# BaseModuleTop.net
KiCad netlist of a schematic drawn in Altium Designer
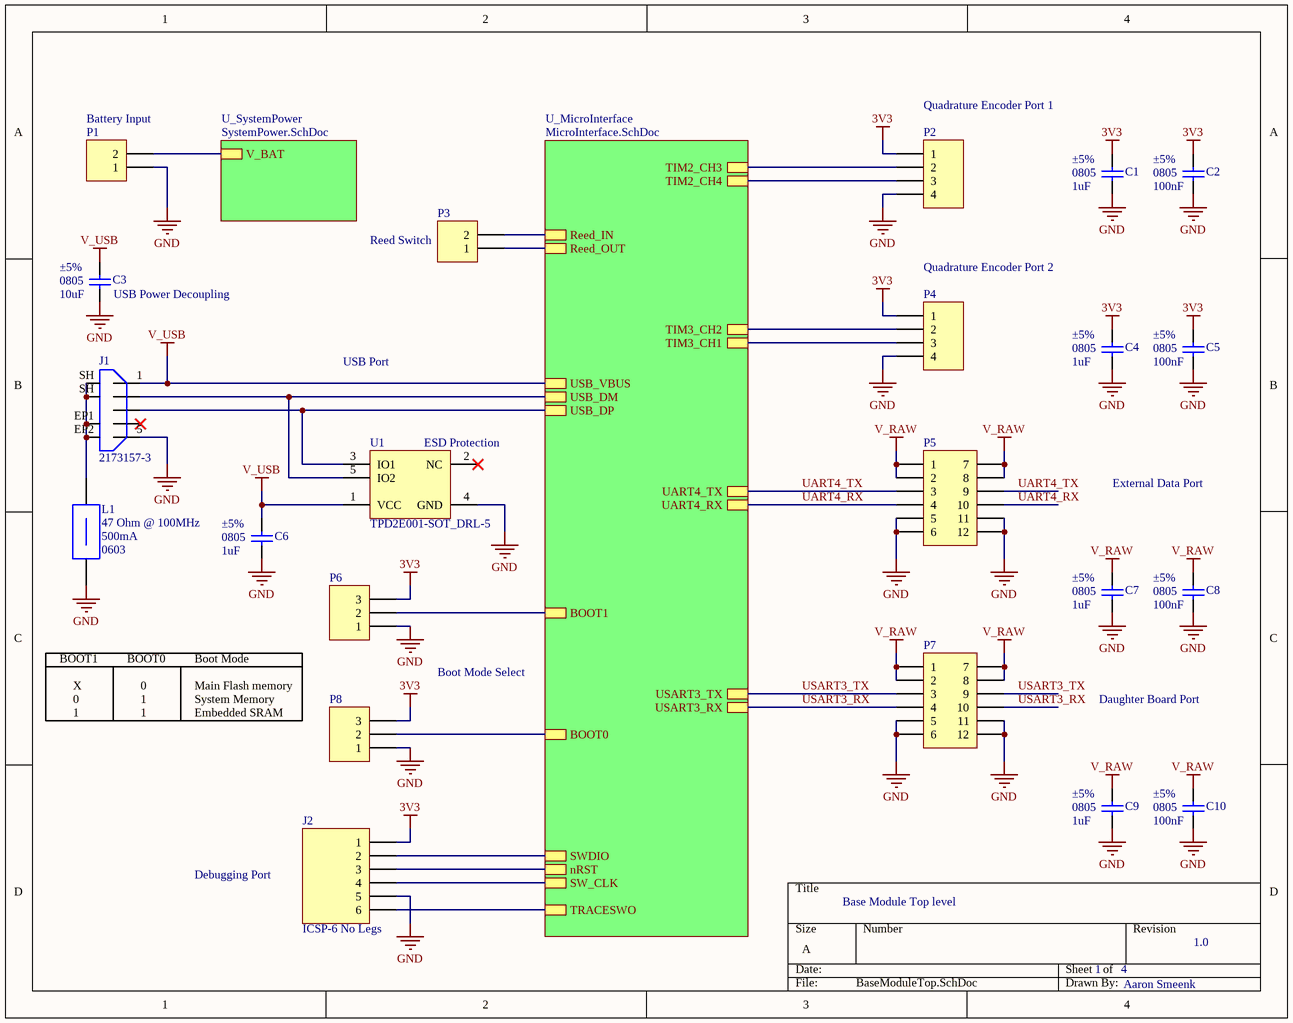
[diagram p0: BaseModuleTop.SchDoc]

(export (version "E")
  (design (tool "Eeschema 10.0.6"))
  (components
    (comp (ref "C1")
      (value "1uF")
      (footprint "CAPC0805(2012)100_L")
      (description "CAP 1uF 6.3V ±5% 0805 (2012 Metric) Thickness 1mm SMD")
      (fields
        (field (name "TOLERANCE") "±5%")
        (field (name "CASE-EIA") "0805")
        (field (name "Comment") "CAP 1uF 6.3V 0805(2012)")
      )
      (libsource (lib "Altium Content Vault") (part "CMP-1036-04730-1"))
    )
    (comp (ref "C2")
      (value "100nF")
      (footprint "CAPC0805(2012)100_M")
      (description "CAP 100nF 6.3V ±5% 0805 (2012 Metric) Thickness 1mm SMD")
      (fields
        (field (name "TOLERANCE") "±5%")
        (field (name "CASE-EIA") "0805")
        (field (name "Comment") "CAP 100nF 6.3V 0805(2012)")
      )
      (libsource (lib "Altium Content Vault") (part "CMP-1036-04390-1"))
    )
    (comp (ref "C3")
      (value "10uF")
      (footprint "CAPC0805(2012)100_L")
      (description "CAP 10uF 6.3V ±5% 0805 (2012 Metric) Thickness 1mm SMD")
      (fields
        (field (name "TOLERANCE") "±5%")
        (field (name "CASE-EIA") "0805")
        (field (name "Comment") "CAP 10uF 6.3V 0805(2012)")
      )
      (libsource (lib "Altium Content Vault") (part "CMP-1036-04730-1"))
    )
    (comp (ref "C4")
      (value "1uF")
      (footprint "CAPC0805(2012)100_L")
      (description "CAP 1uF 6.3V ±5% 0805 (2012 Metric) Thickness 1mm SMD")
      (fields
        (field (name "TOLERANCE") "±5%")
        (field (name "CASE-EIA") "0805")
        (field (name "Comment") "CAP 1uF 6.3V 0805(2012)")
      )
      (libsource (lib "Altium Content Vault") (part "CMP-1036-04730-1"))
    )
    (comp (ref "C5")
      (value "100nF")
      (footprint "CAPC0805(2012)100_M")
      (description "CAP 100nF 6.3V ±5% 0805 (2012 Metric) Thickness 1mm SMD")
      (fields
        (field (name "TOLERANCE") "±5%")
        (field (name "CASE-EIA") "0805")
        (field (name "Comment") "CAP 100nF 6.3V 0805(2012)")
      )
      (libsource (lib "Altium Content Vault") (part "CMP-1036-04390-1"))
    )
    (comp (ref "C6")
      (value "1uF")
      (footprint "CAPC0805(2012)100_L")
      (description "CAP 1uF 6.3V ±5% 0805 (2012 Metric) Thickness 1mm SMD")
      (fields
        (field (name "TOLERANCE") "±5%")
        (field (name "CASE-EIA") "0805")
        (field (name "Comment") "CAP 1uF 6.3V 0805(2012)")
      )
      (libsource (lib "Altium Content Vault") (part "CMP-1036-04730-1"))
    )
    (comp (ref "C7")
      (value "1uF")
      (footprint "CAPC0805(2012)100_L")
      (description "CAP 1uF 6.3V ±5% 0805 (2012 Metric) Thickness 1mm SMD")
      (fields
        (field (name "TOLERANCE") "±5%")
        (field (name "CASE-EIA") "0805")
        (field (name "Comment") "CAP 1uF 6.3V 0805(2012)")
      )
      (libsource (lib "Altium Content Vault") (part "CMP-1036-04730-1"))
    )
    (comp (ref "C8")
      (value "100nF")
      (footprint "CAPC0805(2012)100_M")
      (description "CAP 100nF 6.3V ±5% 0805 (2012 Metric) Thickness 1mm SMD")
      (fields
        (field (name "TOLERANCE") "±5%")
        (field (name "CASE-EIA") "0805")
        (field (name "Comment") "CAP 100nF 6.3V 0805(2012)")
      )
      (libsource (lib "Altium Content Vault") (part "CMP-1036-04390-1"))
    )
    (comp (ref "C9")
      (value "1uF")
      (footprint "CAPC0805(2012)100_L")
      (description "CAP 1uF 6.3V ±5% 0805 (2012 Metric) Thickness 1mm SMD")
      (fields
        (field (name "TOLERANCE") "±5%")
        (field (name "CASE-EIA") "0805")
        (field (name "Comment") "CAP 1uF 6.3V 0805(2012)")
      )
      (libsource (lib "Altium Content Vault") (part "CMP-1036-04730-1"))
    )
    (comp (ref "C10")
      (value "100nF")
      (footprint "CAPC0805(2012)100_M")
      (description "CAP 100nF 6.3V ±5% 0805 (2012 Metric) Thickness 1mm SMD")
      (fields
        (field (name "TOLERANCE") "±5%")
        (field (name "CASE-EIA") "0805")
        (field (name "Comment") "CAP 100nF 6.3V 0805(2012)")
      )
      (libsource (lib "Altium Content Vault") (part "CMP-1036-04390-1"))
    )
    (comp (ref "J1")
      (value "2173157-3")
      (footprint "2173157-3")
      (description "USB Connectors SPLASH PROOF MICRO 5P USB B-TYPE")
      (libsource (lib "schlib") (part "2173157-3"))
    )
    (comp (ref "J2")
      (value "ICSP-6 No Legs")
      (footprint "TC2030-IDC-NL")
      (description "6 Pin Connector")
      (libsource (lib "schlib") (part "ICSP-6 No Legs"))
    )
    (comp (ref "L1")
      (value "LI0603E470R-10")
      (footprint "LI0603E470R-10")
      (description "FERRITE CHIP 47 OHMS 500MA 0603")
      (fields
        (field (name "IMPEDANCE @ FREQUENCY") "47 Ohm @ 100MHz")
        (field (name "CURRENT RATING") "500mA")
        (field (name "PACKAGE / CASE") "0603")
      )
      (libsource (lib "schlib") (part "LI0603E470R-10"))
    )
    (comp (ref "P1")
      (value "Header 2")
      (footprint "HDR1X2")
      (description "Header, 2-Pin")
      (fields (field (name "PUBLISHER") "Altium Limited"))
      (libsource (lib "Miscellaneous Connectors") (part "Header 2"))
    )
    (comp (ref "P2")
      (value "Header 4")
      (footprint "HDR1X4")
      (description "Header, 4-Pin")
      (fields (field (name "PUBLISHER") "Altium Limited"))
      (libsource (lib "Miscellaneous Connectors") (part "Header 4"))
    )
    (comp (ref "P3")
      (value "Header 2")
      (footprint "HDR1X2")
      (description "Header, 2-Pin")
      (fields (field (name "PUBLISHER") "Altium Limited"))
      (libsource (lib "Miscellaneous Connectors") (part "Header 2"))
    )
    (comp (ref "P4")
      (value "Header 4")
      (footprint "HDR1X4")
      (description "Header, 4-Pin")
      (fields (field (name "PUBLISHER") "Altium Limited"))
      (libsource (lib "Miscellaneous Connectors") (part "Header 4"))
    )
    (comp (ref "P5")
      (value "Header 6X2A")
      (footprint "HDR2X6_CEN")
      (description "Header, 6-Pin, Dual row")
      (fields (field (name "PUBLISHER") "Altium Limited"))
      (libsource (lib "Miscellaneous Connectors") (part "Header 6X2A"))
    )
    (comp (ref "P6")
      (value "Header 3")
      (footprint "HDR1X3")
      (description "Header, 3-Pin")
      (fields (field (name "PUBLISHER") "Altium Limited"))
      (libsource (lib "Miscellaneous Connectors") (part "Header 3"))
    )
    (comp (ref "P7")
      (value "Header 6X2A")
      (footprint "HDR2X6_CEN")
      (description "Header, 6-Pin, Dual row")
      (fields (field (name "PUBLISHER") "Altium Limited"))
      (libsource (lib "Miscellaneous Connectors") (part "Header 6X2A"))
    )
    (comp (ref "P8")
      (value "Header 3")
      (footprint "HDR1X3")
      (description "Header, 3-Pin")
      (fields (field (name "PUBLISHER") "Altium Limited"))
      (libsource (lib "Miscellaneous Connectors") (part "Header 3"))
    )
    (comp (ref "U1")
      (value "TPD2E001-SOT_DRL-5")
      (footprint "TPD2E001DRLR")
      (description "TVS DIODE 5.5VWM 100VC SOT5")
      (libsource (lib "schlib") (part "TPD2E001DRLR"))
    )
  )
  (nets
    (net (code "1") (name "/BOOT0") (class "Default")
      (node (ref "P8") (pin "2") (pinfunction "2_2") (pintype "passive"))
    )
    (net (code "2") (name "/BOOT1") (class "Default")
      (node (ref "P6") (pin "2") (pinfunction "2_2") (pintype "passive"))
    )
    (net (code "3") (name "/Reed_IN") (class "Default")
      (node (ref "P3") (pin "2") (pinfunction "2_2") (pintype "passive"))
    )
    (net (code "4") (name "/Reed_OUT") (class "Default")
      (node (ref "P3") (pin "1") (pinfunction "1_1") (pintype "passive"))
    )
    (net (code "5") (name "/SWDIO") (class "Default")
      (node (ref "J2") (pin "2") (pinfunction "2_2") (pintype "passive"))
    )
    (net (code "6") (name "/SW_CLK") (class "Default")
      (node (ref "J2") (pin "4") (pinfunction "4_4") (pintype "passive"))
    )
    (net (code "7") (name "/TIM2_CH3") (class "Default")
      (node (ref "P2") (pin "2") (pinfunction "2_2") (pintype "passive"))
    )
    (net (code "8") (name "/TIM2_CH4") (class "Default")
      (node (ref "P2") (pin "3") (pinfunction "3_3") (pintype "passive"))
    )
    (net (code "9") (name "/TIM3_CH1") (class "Default")
      (node (ref "P4") (pin "3") (pinfunction "3_3") (pintype "passive"))
    )
    (net (code "10") (name "/TIM3_CH2") (class "Default")
      (node (ref "P4") (pin "2") (pinfunction "2_2") (pintype "passive"))
    )
    (net (code "11") (name "/TRACESWO") (class "Default")
      (node (ref "J2") (pin "6") (pinfunction "6_6") (pintype "passive"))
    )
    (net (code "12") (name "/UART4_RX") (class "Default")
      (node (ref "P5") (pin "10") (pinfunction "10_10") (pintype "passive"))
      (node (ref "P5") (pin "4") (pinfunction "4_4") (pintype "passive"))
    )
    (net (code "13") (name "/UART4_TX") (class "Default")
      (node (ref "P5") (pin "3") (pinfunction "3_3") (pintype "passive"))
      (node (ref "P5") (pin "9") (pinfunction "9_9") (pintype "passive"))
    )
    (net (code "14") (name "/USART3_RX") (class "Default")
      (node (ref "P7") (pin "10") (pinfunction "10_10") (pintype "passive"))
      (node (ref "P7") (pin "4") (pinfunction "4_4") (pintype "passive"))
    )
    (net (code "15") (name "/USART3_TX") (class "Default")
      (node (ref "P7") (pin "3") (pinfunction "3_3") (pintype "passive"))
      (node (ref "P7") (pin "9") (pinfunction "9_9") (pintype "passive"))
    )
    (net (code "16") (name "/USB_DM") (class "Default")
      (node (ref "J1") (pin "2") (pinfunction "D-_2") (pintype "passive"))
      (node (ref "U1") (pin "5") (pinfunction "IO2_5") (pintype "passive"))
    )
    (net (code "17") (name "/USB_DP") (class "Default")
      (node (ref "J1") (pin "3") (pinfunction "D+_3") (pintype "passive"))
      (node (ref "U1") (pin "3") (pinfunction "IO1_3") (pintype "passive"))
    )
    (net (code "18") (name "/V_BAT") (class "Default")
      (node (ref "P1") (pin "2") (pinfunction "2_2") (pintype "passive"))
    )
    (net (code "19") (name "/nRST") (class "Default")
      (node (ref "J2") (pin "3") (pinfunction "3_3") (pintype "passive"))
    )
    (net (code "20") (name "3V3") (class "Default")
      (node (ref "C1") (pin "2") (pinfunction "2_2") (pintype "passive"))
      (node (ref "C2") (pin "2") (pinfunction "2_2") (pintype "passive"))
      (node (ref "C4") (pin "2") (pinfunction "2_2") (pintype "passive"))
      (node (ref "C5") (pin "2") (pinfunction "2_2") (pintype "passive"))
      (node (ref "J2") (pin "1") (pinfunction "1_1") (pintype "passive"))
      (node (ref "P2") (pin "1") (pinfunction "1_1") (pintype "passive"))
      (node (ref "P4") (pin "1") (pinfunction "1_1") (pintype "passive"))
      (node (ref "P6") (pin "3") (pinfunction "3_3") (pintype "passive"))
      (node (ref "P8") (pin "3") (pinfunction "3_3") (pintype "passive"))
    )
    (net (code "21") (name "GND") (class "Default")
      (node (ref "C1") (pin "1") (pinfunction "1_1") (pintype "passive"))
      (node (ref "C10") (pin "1") (pinfunction "1_1") (pintype "passive"))
      (node (ref "C2") (pin "1") (pinfunction "1_1") (pintype "passive"))
      (node (ref "C3") (pin "1") (pinfunction "1_1") (pintype "passive"))
      (node (ref "C4") (pin "1") (pinfunction "1_1") (pintype "passive"))
      (node (ref "C5") (pin "1") (pinfunction "1_1") (pintype "passive"))
      (node (ref "C6") (pin "1") (pinfunction "1_1") (pintype "passive"))
      (node (ref "C7") (pin "1") (pinfunction "1_1") (pintype "passive"))
      (node (ref "C8") (pin "1") (pinfunction "1_1") (pintype "passive"))
      (node (ref "C9") (pin "1") (pinfunction "1_1") (pintype "passive"))
      (node (ref "J1") (pin "5") (pinfunction "GND_5") (pintype "passive"))
      (node (ref "J2") (pin "5") (pinfunction "5_5") (pintype "passive"))
      (node (ref "L1") (pin "1") (pinfunction "1_1") (pintype "passive"))
      (node (ref "P1") (pin "1") (pinfunction "1_1") (pintype "passive"))
      (node (ref "P2") (pin "4") (pinfunction "4_4") (pintype "passive"))
      (node (ref "P4") (pin "4") (pinfunction "4_4") (pintype "passive"))
      (node (ref "P5") (pin "11") (pinfunction "11_11") (pintype "passive"))
      (node (ref "P5") (pin "12") (pinfunction "12_12") (pintype "passive"))
      (node (ref "P5") (pin "5") (pinfunction "5_5") (pintype "passive"))
      (node (ref "P5") (pin "6") (pinfunction "6_6") (pintype "passive"))
      (node (ref "P6") (pin "1") (pinfunction "1_1") (pintype "passive"))
      (node (ref "P7") (pin "11") (pinfunction "11_11") (pintype "passive"))
      (node (ref "P7") (pin "12") (pinfunction "12_12") (pintype "passive"))
      (node (ref "P7") (pin "5") (pinfunction "5_5") (pintype "passive"))
      (node (ref "P7") (pin "6") (pinfunction "6_6") (pintype "passive"))
      (node (ref "P8") (pin "1") (pinfunction "1_1") (pintype "passive"))
      (node (ref "U1") (pin "4") (pinfunction "GND_4") (pintype "power_in"))
    )
    (net (code "22") (name "Net-(J1-PadEP1)") (class "Default")
      (node (ref "J1") (pin "EP1") (pinfunction "EP1_EP1") (pintype "passive"))
      (node (ref "J1") (pin "EP2") (pinfunction "EP2_EP2") (pintype "passive"))
      (node (ref "J1") (pin "SH") (pinfunction "SH_SH") (pintype "passive"))
      (node (ref "L1") (pin "2") (pinfunction "2_2") (pintype "passive"))
    )
    (net (code "23") (name "V_RAW") (class "Default")
      (node (ref "C10") (pin "2") (pinfunction "2_2") (pintype "passive"))
      (node (ref "C7") (pin "2") (pinfunction "2_2") (pintype "passive"))
      (node (ref "C8") (pin "2") (pinfunction "2_2") (pintype "passive"))
      (node (ref "C9") (pin "2") (pinfunction "2_2") (pintype "passive"))
      (node (ref "P5") (pin "1") (pinfunction "1_1") (pintype "passive"))
      (node (ref "P5") (pin "2") (pinfunction "2_2") (pintype "passive"))
      (node (ref "P5") (pin "7") (pinfunction "7_7") (pintype "passive"))
      (node (ref "P5") (pin "8") (pinfunction "8_8") (pintype "passive"))
      (node (ref "P7") (pin "1") (pinfunction "1_1") (pintype "passive"))
      (node (ref "P7") (pin "2") (pinfunction "2_2") (pintype "passive"))
      (node (ref "P7") (pin "7") (pinfunction "7_7") (pintype "passive"))
      (node (ref "P7") (pin "8") (pinfunction "8_8") (pintype "passive"))
    )
    (net (code "24") (name "V_USB") (class "Default")
      (node (ref "C3") (pin "2") (pinfunction "2_2") (pintype "passive"))
      (node (ref "C6") (pin "2") (pinfunction "2_2") (pintype "passive"))
      (node (ref "J1") (pin "1") (pinfunction "5V_1") (pintype "passive"))
      (node (ref "U1") (pin "1") (pinfunction "VCC_1") (pintype "power_in"))
    )
    (net (code "25") (name "unconnected-(J1-ID-Pad4)") (class "Default")
      (node (ref "J1") (pin "4") (pinfunction "ID_4") (pintype "passive+no_connect"))
    )
    (net (code "26") (name "unconnected-(U1-NC-Pad2)") (class "Default")
      (node (ref "U1") (pin "2") (pinfunction "NC_2") (pintype "passive+no_connect"))
    )
  )
)
